# crystal-test-breakout-mk-2.net
KiCad netlist of a schematic drawn in EAGLE
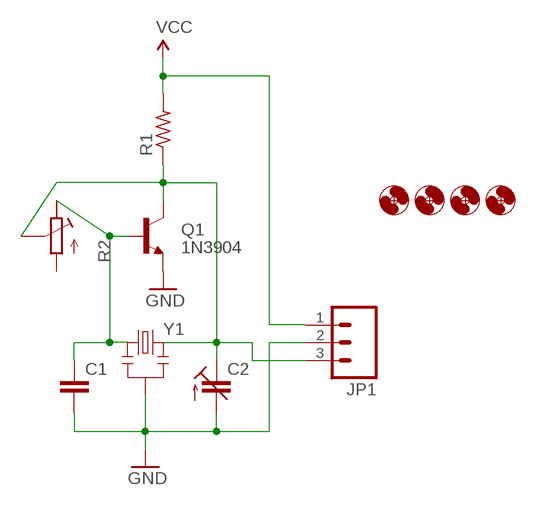
[diagram p0: schematic, sheet 1]

(export (version "E")
  (design (tool "Eeschema 10.0.6"))
  (components
    (comp (ref "C1")
      (value "CAPACITOR-CERAMIC025-025X050")
      (footprint "eagle-import:C025-025X050")
      (libsource (lib "eagle-import") (part "CAPACITOR-CERAMIC025-025X050"))
    )
    (comp (ref "C2")
      (value "CAPACITOR-TRIM3040.427")
      (footprint "eagle-import:CTRIM3040.427")
      (libsource (lib "eagle-import") (part "CAPACITOR-TRIM3040.427"))
    )
    (comp (ref "H1")
      (value "HOLE#2")
      (footprint "eagle-import:HOLE-#2")
      (libsource (lib "eagle-import") (part "HOLE#2"))
    )
    (comp (ref "H2")
      (value "HOLE#2")
      (footprint "eagle-import:HOLE-#2")
      (libsource (lib "eagle-import") (part "HOLE#2"))
    )
    (comp (ref "H3")
      (value "HOLE#2")
      (footprint "eagle-import:HOLE-#2")
      (libsource (lib "eagle-import") (part "HOLE#2"))
    )
    (comp (ref "H4")
      (value "HOLE#2")
      (footprint "eagle-import:HOLE-#2")
      (libsource (lib "eagle-import") (part "HOLE#2"))
    )
    (comp (ref "JP1")
      (value "M03PTH")
      (footprint "eagle-import:1X03")
      (libsource (lib "eagle-import") (part "M03PTH"))
    )
    (comp (ref "Q1")
      (value "1N3904")
      (footprint "eagle-import:TO-92-AMMO")
      (libsource (lib "eagle-import") (part "TRANSISTOR_NPNTO-92-AMMO-EBC"))
    )
    (comp (ref "R1")
      (value "RESISTORPTH-AXIAL-5.08MM")
      (footprint "eagle-import:RESISTOR-AXIAL-PTH-5.08MM")
      (libsource (lib "eagle-import") (part "RESISTORPTH-AXIAL-5.08MM"))
    )
    (comp (ref "R2")
      (value "POTENTIOMETER3296W")
      (footprint "eagle-import:RTRIM3296W")
      (libsource (lib "eagle-import") (part "POTENTIOMETER3296W"))
    )
    (comp (ref "Y1")
      (value "RESONATORPTH-BIGHOLES")
      (footprint "eagle-import:RESONATOR-PTH-BIGHOLES")
      (libsource (lib "eagle-import") (part "RESONATORPTH-BIGHOLES"))
    )
  )
  (nets
    (net (code "1") (name "GND") (class "Default")
      (node (ref "C1") (pin "2") (pinfunction "2_2") (pintype "passive"))
      (node (ref "C2") (pin "2") (pinfunction "A_2") (pintype "passive"))
      (node (ref "JP1") (pin "2") (pinfunction "2_2") (pintype "passive"))
      (node (ref "Q1") (pin "1") (pinfunction "E_1") (pintype "passive"))
      (node (ref "Y1") (pin "2") (pinfunction "2_2") (pintype "passive"))
    )
    (net (code "2") (name "Net-(Q1-B)") (class "Default")
      (node (ref "C1") (pin "1") (pinfunction "1_1") (pintype "passive"))
      (node (ref "Q1") (pin "2") (pinfunction "B_2") (pintype "passive"))
      (node (ref "R2") (pin "3") (pinfunction "E_3") (pintype "passive"))
      (node (ref "Y1") (pin "1") (pinfunction "1_1") (pintype "passive"))
    )
    (net (code "3") (name "Net-(Q1-C)") (class "Default")
      (node (ref "C2") (pin "1A") (pinfunction "E_1A") (pintype "passive"))
      (node (ref "C2") (pin "1B") (pinfunction "E_1B") (pintype "passive"))
      (node (ref "JP1") (pin "3") (pinfunction "3_3") (pintype "passive"))
      (node (ref "Q1") (pin "3") (pinfunction "C_3") (pintype "passive"))
      (node (ref "R1") (pin "P$1") (pinfunction "1_P$1") (pintype "passive"))
      (node (ref "R2") (pin "2") (pinfunction "S_2") (pintype "passive"))
      (node (ref "Y1") (pin "3") (pinfunction "3_3") (pintype "passive"))
    )
    (net (code "4") (name "VCC") (class "Default")
      (node (ref "JP1") (pin "1") (pinfunction "1_1") (pintype "passive"))
      (node (ref "R1") (pin "P$2") (pinfunction "2_P$2") (pintype "passive"))
    )
    (net (code "5") (name "unconnected-(R2-A-Pad1)") (class "Default")
      (node (ref "R2") (pin "1") (pinfunction "A_1") (pintype "passive"))
    )
  )
)
